# 3V3_LDO.net
KiCad netlist of a schematic drawn in Altium Designer
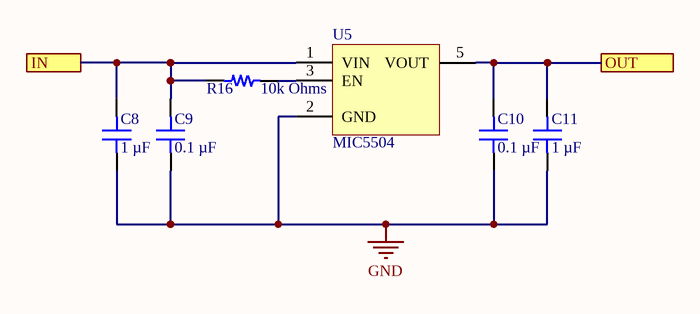
[diagram p0: 3V3_LDO.SchDoc]

(export (version "E")
  (design (tool "Eeschema 10.0.6"))
  (components
    (comp (ref "C8")
      (value "1 µF")
      (footprint "CAP 0402_1005")
      (description "CAP CER 0.1UF 16V X7R 0402")
      (fields (field (name "PART NUMBER") "C0402C104K4RACAUTO") (field (name "MANUFACTURER") "KEMET"))
      (libsource (lib "Celestial Altium Library - altium_library") (part "Capacitor"))
    )
    (comp (ref "C9")
      (value "0.1 µF")
      (footprint "CAP 0402_1005")
      (description "CAP CER 0.1UF 16V X7R 0402")
      (fields (field (name "PART NUMBER") "C0402C104K4RACAUTO") (field (name "MANUFACTURER") "KEMET"))
      (libsource (lib "Celestial Altium Library - altium_library") (part "Capacitor"))
    )
    (comp (ref "C10")
      (value "0.1 µF")
      (footprint "CAP 0402_1005")
      (description "CAP CER 0.1UF 16V X7R 0402")
      (fields (field (name "PART NUMBER") "C0402C104K4RACAUTO") (field (name "MANUFACTURER") "KEMET"))
      (libsource (lib "Celestial Altium Library - altium_library") (part "Capacitor"))
    )
    (comp (ref "C11")
      (value "1 µF")
      (footprint "CAP 0402_1005")
      (description "CAP CER 0.1UF 16V X7R 0402")
      (fields (field (name "PART NUMBER") "C0402C104K4RACAUTO") (field (name "MANUFACTURER") "KEMET"))
      (libsource (lib "Celestial Altium Library - altium_library") (part "Capacitor"))
    )
    (comp (ref "R16")
      (value "10k Ohms")
      (footprint "RES 0402_1005")
      (description "RES 330 OHM 5% 1/16W 0402")
      (fields (field (name "PART NUMBER") "CRCW0402330RJNEDC") (field (name "MANUFACTURER") "Vishay Dale"))
      (libsource (lib "Celestial Altium Library - altium_library") (part "Resistor"))
    )
    (comp (ref "U5")
      (value "MIC5504")
      (footprint "TI SOT-23-5 DBV")
      (description "3.3V LDO")
      (libsource (lib "IC") (part "MIC5504-3.3YM5"))
    )
  )
  (nets
    (net (code "1") (name "/IN") (class "Default")
      (node (ref "C8") (pin "2") (pinfunction "2_2") (pintype "passive"))
      (node (ref "C9") (pin "2") (pinfunction "2_2") (pintype "passive"))
      (node (ref "R16") (pin "2") (pinfunction "2_2") (pintype "passive"))
      (node (ref "U5") (pin "1") (pinfunction "VIN_1") (pintype "passive"))
    )
    (net (code "2") (name "/OUT") (class "Default")
      (node (ref "C10") (pin "2") (pinfunction "2_2") (pintype "passive"))
      (node (ref "C11") (pin "2") (pinfunction "2_2") (pintype "passive"))
      (node (ref "U5") (pin "5") (pinfunction "VOUT_5") (pintype "passive"))
    )
    (net (code "3") (name "GND") (class "Default")
      (node (ref "C10") (pin "1") (pinfunction "1_1") (pintype "passive"))
      (node (ref "C11") (pin "1") (pinfunction "1_1") (pintype "passive"))
      (node (ref "C8") (pin "1") (pinfunction "1_1") (pintype "passive"))
      (node (ref "C9") (pin "1") (pinfunction "1_1") (pintype "passive"))
      (node (ref "U5") (pin "2") (pinfunction "GND_2") (pintype "passive"))
    )
    (net (code "4") (name "Net-(U5-EN)") (class "Default")
      (node (ref "R16") (pin "1") (pinfunction "1_1") (pintype "passive"))
      (node (ref "U5") (pin "3") (pinfunction "EN_3") (pintype "passive"))
    )
  )
)
